# Main_Diagram.net
KiCad netlist of a schematic drawn in Altium Designer
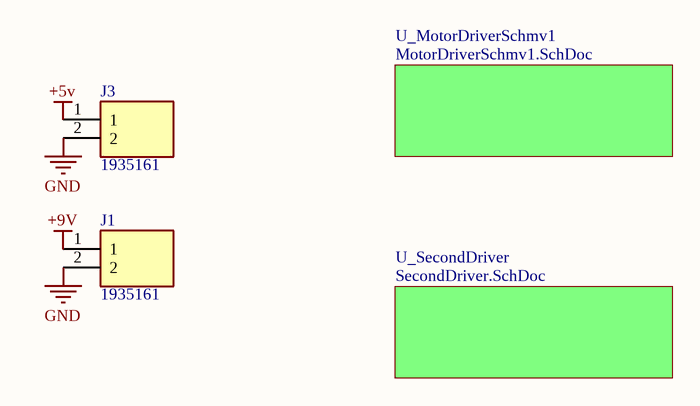
[diagram p0: Main_Diagram.SchDoc]

(export (version "E")
  (design (tool "Eeschema 10.0.6"))
  (components
    (comp (ref "J1")
      (value "1935161")
      (footprint "SamacSys:1935161")
      (description "Connector")
      (fields (field (name "MOUSER PART NUMBER") "651-1935161"))
      (libsource (lib "*") (part "1935161"))
    )
    (comp (ref "J3")
      (value "1935161")
      (footprint "SamacSys:1935161")
      (description "Connector")
      (fields (field (name "MOUSER PART NUMBER") "651-1935161"))
      (libsource (lib "*") (part "1935161"))
    )
  )
  (nets
    (net (code "1") (name "+5v") (class "Default")
      (node (ref "J3") (pin "1") (pinfunction "1_1") (pintype "passive"))
    )
    (net (code "2") (name "+9V") (class "Default")
      (node (ref "J1") (pin "1") (pinfunction "1_1") (pintype "passive"))
    )
    (net (code "3") (name "GND") (class "Default")
      (node (ref "J1") (pin "2") (pinfunction "2_2") (pintype "passive"))
      (node (ref "J3") (pin "2") (pinfunction "2_2") (pintype "passive"))
    )
  )
)
